# Sheet4.net
KiCad netlist of a schematic drawn in Altium Designer
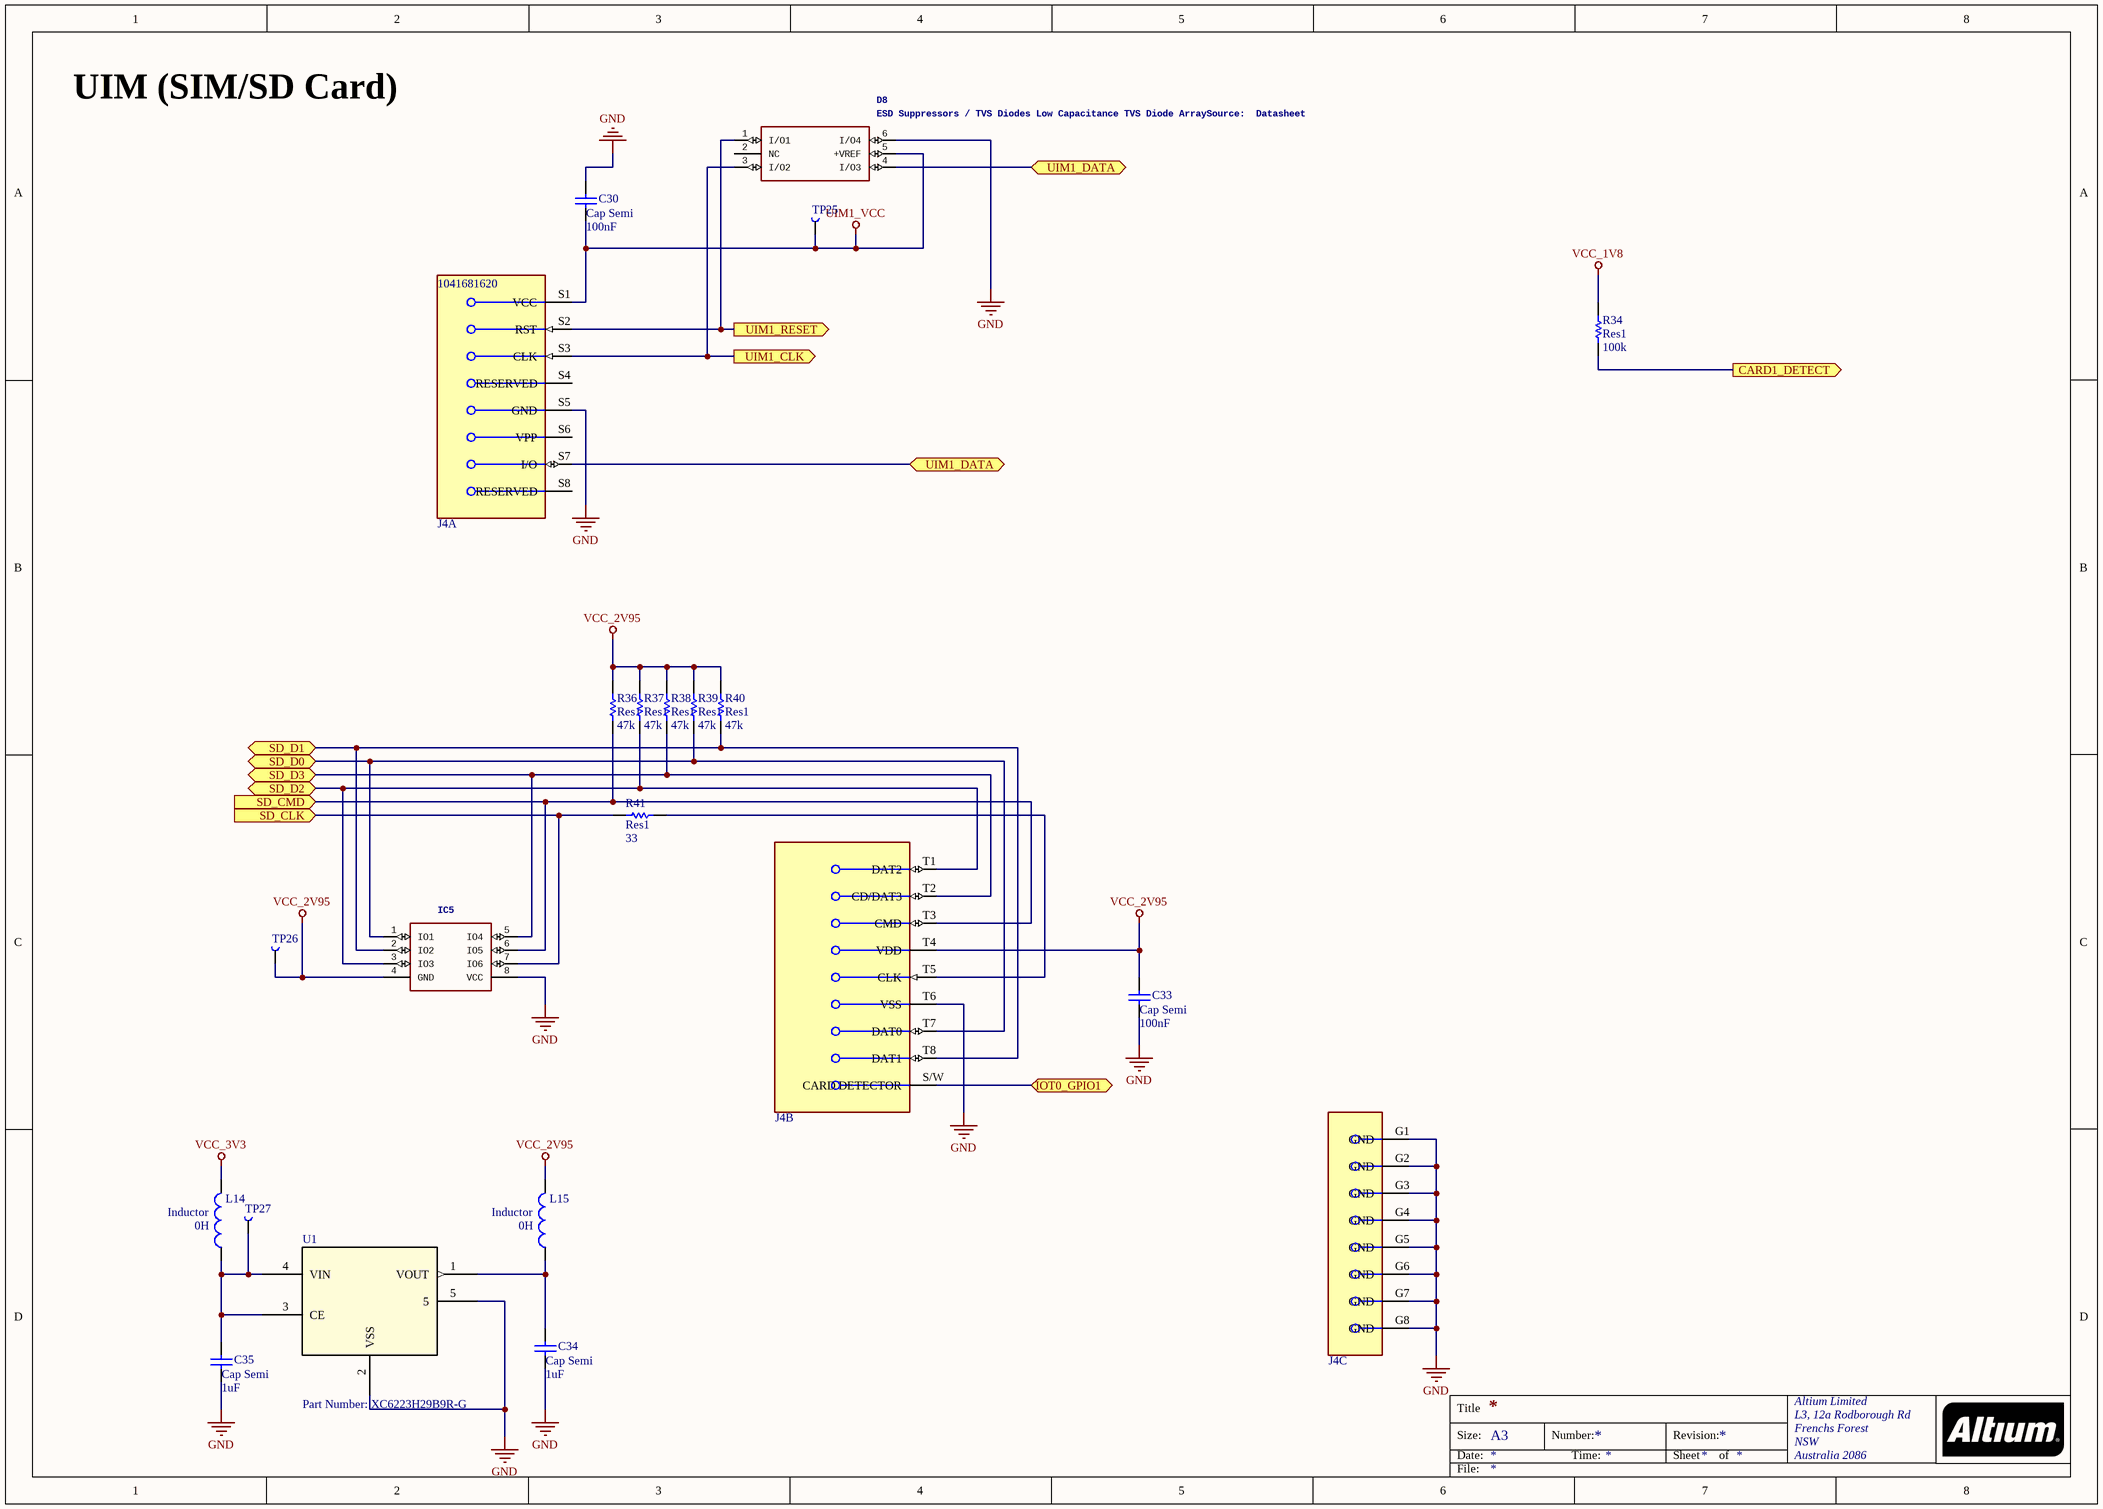
[diagram p0: Sheet4.SchDoc]

(export (version "E")
  (design (tool "Eeschema 10.0.6"))
  (components
    (comp (ref "C30")
      (value "Cap Semi")
      (footprint "CAP 0402/1005")
      (description "0.1µF -20%, +80% 16V Ceramic Capacitor Y5V (F) 0402 (1005 Metric)")
      (fields (field (name "PART NUMBER") "VJ0402V104ZXJCW1BC") (field (name "ALTIUM_VALUE") "100nF"))
      (libsource (lib "Miscellaneous Devices") (part "Cap Semi"))
    )
    (comp (ref "C33")
      (value "Cap Semi")
      (footprint "CAP 0402/1005")
      (description "0.1µF -20%, +80% 16V Ceramic Capacitor Y5V (F) 0402 (1005 Metric)")
      (fields (field (name "PART NUMBER") "VJ0402V104ZXJCW1BC") (field (name "ALTIUM_VALUE") "100nF"))
      (libsource (lib "Miscellaneous Devices") (part "Cap Semi"))
    )
    (comp (ref "C34")
      (value "Cap Semi")
      (footprint "CAP 0402/1005")
      (description "1µF ±10% 10V Ceramic Capacitor X5R 0402 (1005 Metric)")
      (fields (field (name "PART NUMBER") "GRM155R61A105KE15D") (field (name "ALTIUM_VALUE") "1uF"))
      (libsource (lib "Miscellaneous Devices") (part "Cap Semi"))
    )
    (comp (ref "C35")
      (value "Cap Semi")
      (footprint "CAP 0402/1005")
      (description "1µF ±10% 10V Ceramic Capacitor X5R 0402 (1005 Metric)")
      (fields (field (name "PART NUMBER") "GRM155R61A105KE15D") (field (name "ALTIUM_VALUE") "1uF"))
      (libsource (lib "Miscellaneous Devices") (part "Cap Semi"))
    )
    (comp (ref "D8")
      (value "ESD Suppressors / TVS Diodes Low Capacitance TVS Diode ArraySource:  Datasheet")
      (footprint "SON50P100X145X65-6N")
      (description "30V Clamp 3A (8/20µs) Ipp Tvs Diode Surface Mount SLP1510N6")
      (fields
        (field (name "MANUFACTURER_PART_NUMBER") "RCLAMP0503N.TCT")
        (field (name "MOUSER_PART_NUMBER") "947-RCLAMP0503N.TCT")
      )
      (libsource (lib "RCLAMP0503N") (part "RCLAMP0503N.TCT"))
    )
    (comp (ref "IC5")
      (value "~")
      (footprint "RSE0008A")
      (description "Clamp  Ipp Tvs Diode Surface Mount 8-UQFN (1.5x1.5)")
      (fields
        (field (name "PART NUMBER") "TPD6E004RSER")
        (field (name "MOUSER_PART_NUMBER") "595-TPD6E004RSER")
      )
      (libsource (lib "TPD6E004RSER") (part "TPD6E004RSER"))
    )
    (comp (ref "J4")
      (value "104168-1620")
      (footprint "Molex_104168-1620_MFG")
      (description "8 Position Card Connector Combo - microSD™, Micro SIM Surface Mount, Right Angle Gold")
      (fields (field (name "PART NUMBER") "1041681620"))
      (libsource (lib "Conn_Molex_104168-1620_eec") (part "104168-1620"))
    )
    (comp (ref "L14")
      (value "Inductor")
      (footprint "INDC1608L")
      (description "220 Ohms @ 100MHz 1 Power Line Ferrite Bead 0603 (1608 Metric) 2.2A 50 mOhm")
      (fields
        (field (name "ALTIUM_VALUE") "0H")
        (field (name "PART NUMBER") "MPZ1608S221ATA00")
        (field (name "PUBLISHER") "Altium Limited")
      )
      (libsource (lib "Miscellaneous Devices") (part "Inductor"))
    )
    (comp (ref "L15")
      (value "Inductor")
      (footprint "INDC1608L")
      (description "220 Ohms @ 100MHz 1 Power Line Ferrite Bead 0603 (1608 Metric) 2.2A 50 mOhm")
      (fields
        (field (name "ALTIUM_VALUE") "0H")
        (field (name "PART NUMBER") "MPZ1608S221ATA00")
        (field (name "PUBLISHER") "Altium Limited")
      )
      (libsource (lib "Miscellaneous Devices") (part "Inductor"))
    )
    (comp (ref "R34")
      (value "Res1")
      (footprint "RES 0402/1005")
      (description "100 kOhms ±1% 0.1W, 1/10W Chip Resistor 0402 (1005 Metric) Automotive AEC-Q200 Thick Film")
      (fields (field (name "PART NUMBER") "RK73H1ETTP1003F") (field (name "ALTIUM_VALUE") "100k"))
      (libsource (lib "Miscellaneous Devices") (part "Res1"))
    )
    (comp (ref "R36")
      (value "Res1")
      (footprint "RES 0402/1005")
      (description "47 kOhms ±5% 0.063W, 1/16W Chip Resistor 0402 (1005 Metric) Moisture Resistant Thick Film")
      (fields (field (name "PART NUMBER") "RC0402JR-0747KL") (field (name "ALTIUM_VALUE") "47k"))
      (libsource (lib "Miscellaneous Devices") (part "Res1"))
    )
    (comp (ref "R37")
      (value "Res1")
      (footprint "RES 0402/1005")
      (description "47 kOhms ±5% 0.063W, 1/16W Chip Resistor 0402 (1005 Metric) Moisture Resistant Thick Film")
      (fields (field (name "PART NUMBER") "RC0402JR-0747KL") (field (name "ALTIUM_VALUE") "47k"))
      (libsource (lib "Miscellaneous Devices") (part "Res1"))
    )
    (comp (ref "R38")
      (value "Res1")
      (footprint "RES 0402/1005")
      (description "47 kOhms ±5% 0.063W, 1/16W Chip Resistor 0402 (1005 Metric) Moisture Resistant Thick Film")
      (fields (field (name "PART NUMBER") "RC0402JR-0747KL") (field (name "ALTIUM_VALUE") "47k"))
      (libsource (lib "Miscellaneous Devices") (part "Res1"))
    )
    (comp (ref "R39")
      (value "Res1")
      (footprint "RES 0402/1005")
      (description "47 kOhms ±5% 0.063W, 1/16W Chip Resistor 0402 (1005 Metric) Moisture Resistant Thick Film")
      (fields (field (name "PART NUMBER") "RC0402JR-0747KL") (field (name "ALTIUM_VALUE") "47k"))
      (libsource (lib "Miscellaneous Devices") (part "Res1"))
    )
    (comp (ref "R40")
      (value "Res1")
      (footprint "RES 0402/1005")
      (description "47 kOhms ±5% 0.063W, 1/16W Chip Resistor 0402 (1005 Metric) Moisture Resistant Thick Film")
      (fields (field (name "PART NUMBER") "RC0402JR-0747KL") (field (name "ALTIUM_VALUE") "47k"))
      (libsource (lib "Miscellaneous Devices") (part "Res1"))
    )
    (comp (ref "R41")
      (value "Res1")
      (footprint "RES 0402/1005")
      (description "33 Ohms ±5% 0.1W, 1/10W Chip Resistor 0402 (1005 Metric) Automotive AEC-Q200 Thick Film")
      (fields (field (name "PART NUMBER") "RK73B1ETTP330J") (field (name "ALTIUM_VALUE") "33"))
      (libsource (lib "Miscellaneous Devices") (part "Res1"))
    )
    (comp (ref "TP25")
      (value "TestPoint")
      (footprint "TestPoint")
      (libsource (lib "TestPoint") (part "TestPoint"))
    )
    (comp (ref "TP26")
      (value "TestPoint")
      (footprint "TestPoint")
      (libsource (lib "TestPoint") (part "TestPoint"))
    )
    (comp (ref "TP27")
      (value "TestPoint")
      (footprint "TestPoint")
      (libsource (lib "TestPoint") (part "TestPoint"))
    )
    (comp (ref "U1")
      (value "Part Number: XC6223H29B9R-G")
      (footprint "USPQ-4B03")
      (description "LDO Voltage Regulators")
      (fields
        (field (name "PART NUMBER") "XC6223H29B9R-G")
        (field (name "COPYRIGHT") "Copyright (C) 2018 Accelerated Designs. All rights reserved")
      )
      (libsource (lib "XC6223H29B9RG") (part "XC6223H29B9R-G"))
    )
  )
  (nets
    (net (code "1") (name "/CARD1_DETECT") (class "Default")
      (node (ref "R34") (pin "2") (pinfunction "2_2") (pintype "passive"))
    )
    (net (code "2") (name "/IOT0_GPIO1") (class "Default")
      (node (ref "J4") (pin "S/W") (pinfunction "CARD_DETECTOR_S/W") (pintype "passive"))
    )
    (net (code "3") (name "/SD_CLK") (class "Default")
      (node (ref "IC5") (pin "7") (pinfunction "IO6_7") (pintype "bidirectional"))
      (node (ref "R41") (pin "2") (pinfunction "2_2") (pintype "passive"))
    )
    (net (code "4") (name "/SD_CMD") (class "Default")
      (node (ref "IC5") (pin "6") (pinfunction "IO5_6") (pintype "bidirectional"))
      (node (ref "J4") (pin "T3") (pinfunction "CMD_T3") (pintype "bidirectional"))
      (node (ref "R36") (pin "1") (pinfunction "1_1") (pintype "passive"))
    )
    (net (code "5") (name "/SD_D0") (class "Default")
      (node (ref "IC5") (pin "1") (pinfunction "IO1_1") (pintype "bidirectional"))
      (node (ref "J4") (pin "T7") (pinfunction "DAT0_T7") (pintype "bidirectional"))
      (node (ref "R39") (pin "1") (pinfunction "1_1") (pintype "passive"))
    )
    (net (code "6") (name "/SD_D1") (class "Default")
      (node (ref "IC5") (pin "2") (pinfunction "IO2_2") (pintype "bidirectional"))
      (node (ref "J4") (pin "T8") (pinfunction "DAT1_T8") (pintype "bidirectional"))
      (node (ref "R40") (pin "1") (pinfunction "1_1") (pintype "passive"))
    )
    (net (code "7") (name "/SD_D2") (class "Default")
      (node (ref "IC5") (pin "3") (pinfunction "IO3_3") (pintype "bidirectional"))
      (node (ref "J4") (pin "T1") (pinfunction "DAT2_T1") (pintype "bidirectional"))
      (node (ref "R37") (pin "1") (pinfunction "1_1") (pintype "passive"))
    )
    (net (code "8") (name "/SD_D3") (class "Default")
      (node (ref "IC5") (pin "5") (pinfunction "IO4_5") (pintype "bidirectional"))
      (node (ref "J4") (pin "T2") (pinfunction "CD/DAT3_T2") (pintype "bidirectional"))
      (node (ref "R38") (pin "1") (pinfunction "1_1") (pintype "passive"))
    )
    (net (code "9") (name "/UIM1_CLK") (class "Default")
      (node (ref "D8") (pin "3") (pinfunction "I/O2_3") (pintype "bidirectional"))
      (node (ref "J4") (pin "S3") (pinfunction "CLK_S3") (pintype "input"))
    )
    (net (code "10") (name "/UIM1_DATA") (class "Default")
      (node (ref "D8") (pin "4") (pinfunction "I/O3_4") (pintype "bidirectional"))
      (node (ref "J4") (pin "S7") (pinfunction "I/O_S7") (pintype "bidirectional"))
    )
    (net (code "11") (name "/UIM1_RESET") (class "Default")
      (node (ref "D8") (pin "1") (pinfunction "I/O1_1") (pintype "bidirectional"))
      (node (ref "J4") (pin "S2") (pinfunction "RST_S2") (pintype "input"))
    )
    (net (code "12") (name "GND") (class "Default")
      (node (ref "C30") (pin "2") (pinfunction "2_2") (pintype "passive"))
      (node (ref "C33") (pin "1") (pinfunction "1_1") (pintype "passive"))
      (node (ref "C34") (pin "1") (pinfunction "1_1") (pintype "passive"))
      (node (ref "C35") (pin "1") (pinfunction "1_1") (pintype "passive"))
      (node (ref "D8") (pin "6") (pinfunction "I/O4_6") (pintype "bidirectional"))
      (node (ref "IC5") (pin "8") (pinfunction "VCC_8") (pintype "power_in"))
      (node (ref "J4") (pin "G1") (pinfunction "GND_G1") (pintype "power_in"))
      (node (ref "J4") (pin "G2") (pinfunction "GND_G2") (pintype "power_in"))
      (node (ref "J4") (pin "G3") (pinfunction "GND_G3") (pintype "power_in"))
      (node (ref "J4") (pin "G4") (pinfunction "GND_G4") (pintype "power_in"))
      (node (ref "J4") (pin "G5") (pinfunction "GND_G5") (pintype "power_in"))
      (node (ref "J4") (pin "G6") (pinfunction "GND_G6") (pintype "power_in"))
      (node (ref "J4") (pin "G7") (pinfunction "GND_G7") (pintype "power_in"))
      (node (ref "J4") (pin "G8") (pinfunction "GND_G8") (pintype "power_in"))
      (node (ref "J4") (pin "S5") (pinfunction "GND_S5") (pintype "power_in"))
      (node (ref "J4") (pin "T6") (pinfunction "VSS_T6") (pintype "power_in"))
      (node (ref "U1") (pin "2") (pinfunction "VSS_2") (pintype "passive"))
      (node (ref "U1") (pin "5") (pinfunction "5_5") (pintype "passive"))
    )
    (net (code "13") (name "Net-(J4B-CLK)") (class "Default")
      (node (ref "J4") (pin "T5") (pinfunction "CLK_T5") (pintype "input"))
      (node (ref "R41") (pin "1") (pinfunction "1_1") (pintype "passive"))
    )
    (net (code "14") (name "Net-(TP27-TP)") (class "Default")
      (node (ref "C35") (pin "2") (pinfunction "2_2") (pintype "passive"))
      (node (ref "L14") (pin "1") (pinfunction "1_1") (pintype "passive"))
      (node (ref "TP27") (pin "1") (pinfunction "TP_1") (pintype "passive"))
      (node (ref "U1") (pin "3") (pinfunction "CE_3") (pintype "passive"))
      (node (ref "U1") (pin "4") (pinfunction "VIN_4") (pintype "power_in"))
    )
    (net (code "15") (name "Net-(U1-VOUT)") (class "Default")
      (node (ref "C34") (pin "2") (pinfunction "2_2") (pintype "passive"))
      (node (ref "L15") (pin "1") (pinfunction "1_1") (pintype "passive"))
      (node (ref "U1") (pin "1") (pinfunction "VOUT_1") (pintype "output"))
    )
    (net (code "16") (name "UIM1_VCC") (class "Default")
      (node (ref "C30") (pin "1") (pinfunction "1_1") (pintype "passive"))
      (node (ref "D8") (pin "5") (pinfunction "+VREF_5") (pintype "bidirectional"))
      (node (ref "J4") (pin "S1") (pinfunction "VCC_S1") (pintype "power_in"))
      (node (ref "TP25") (pin "1") (pinfunction "TP_1") (pintype "passive"))
    )
    (net (code "17") (name "VCC_1V8") (class "Default")
      (node (ref "R34") (pin "1") (pinfunction "1_1") (pintype "passive"))
    )
    (net (code "18") (name "VCC_2V95") (class "Default")
      (node (ref "C33") (pin "2") (pinfunction "2_2") (pintype "passive"))
      (node (ref "IC5") (pin "4") (pinfunction "GND_4") (pintype "power_in"))
      (node (ref "J4") (pin "T4") (pinfunction "VDD_T4") (pintype "power_in"))
      (node (ref "L15") (pin "2") (pinfunction "2_2") (pintype "passive"))
      (node (ref "R36") (pin "2") (pinfunction "2_2") (pintype "passive"))
      (node (ref "R37") (pin "2") (pinfunction "2_2") (pintype "passive"))
      (node (ref "R38") (pin "2") (pinfunction "2_2") (pintype "passive"))
      (node (ref "R39") (pin "2") (pinfunction "2_2") (pintype "passive"))
      (node (ref "R40") (pin "2") (pinfunction "2_2") (pintype "passive"))
      (node (ref "TP26") (pin "1") (pinfunction "TP_1") (pintype "passive"))
    )
    (net (code "19") (name "VCC_3V3") (class "Default")
      (node (ref "L14") (pin "2") (pinfunction "2_2") (pintype "passive"))
    )
    (net (code "20") (name "unconnected-(D8-NC-Pad2)") (class "Default")
      (node (ref "D8") (pin "2") (pinfunction "NC_2") (pintype "passive"))
    )
    (net (code "21") (name "unconnected-(J4A-RESERVED-PadS4)") (class "Default")
      (node (ref "J4") (pin "S4") (pinfunction "RESERVED_S4") (pintype "passive"))
    )
    (net (code "22") (name "unconnected-(J4A-RESERVED-PadS8)") (class "Default")
      (node (ref "J4") (pin "S8") (pinfunction "RESERVED_S8") (pintype "passive"))
    )
    (net (code "23") (name "unconnected-(J4A-VPP-PadS6)") (class "Default")
      (node (ref "J4") (pin "S6") (pinfunction "VPP_S6") (pintype "power_in"))
    )
  )
)
